# Netscale48HD_Microccontroller.net
KiCad netlist of a schematic drawn in Altium Designer
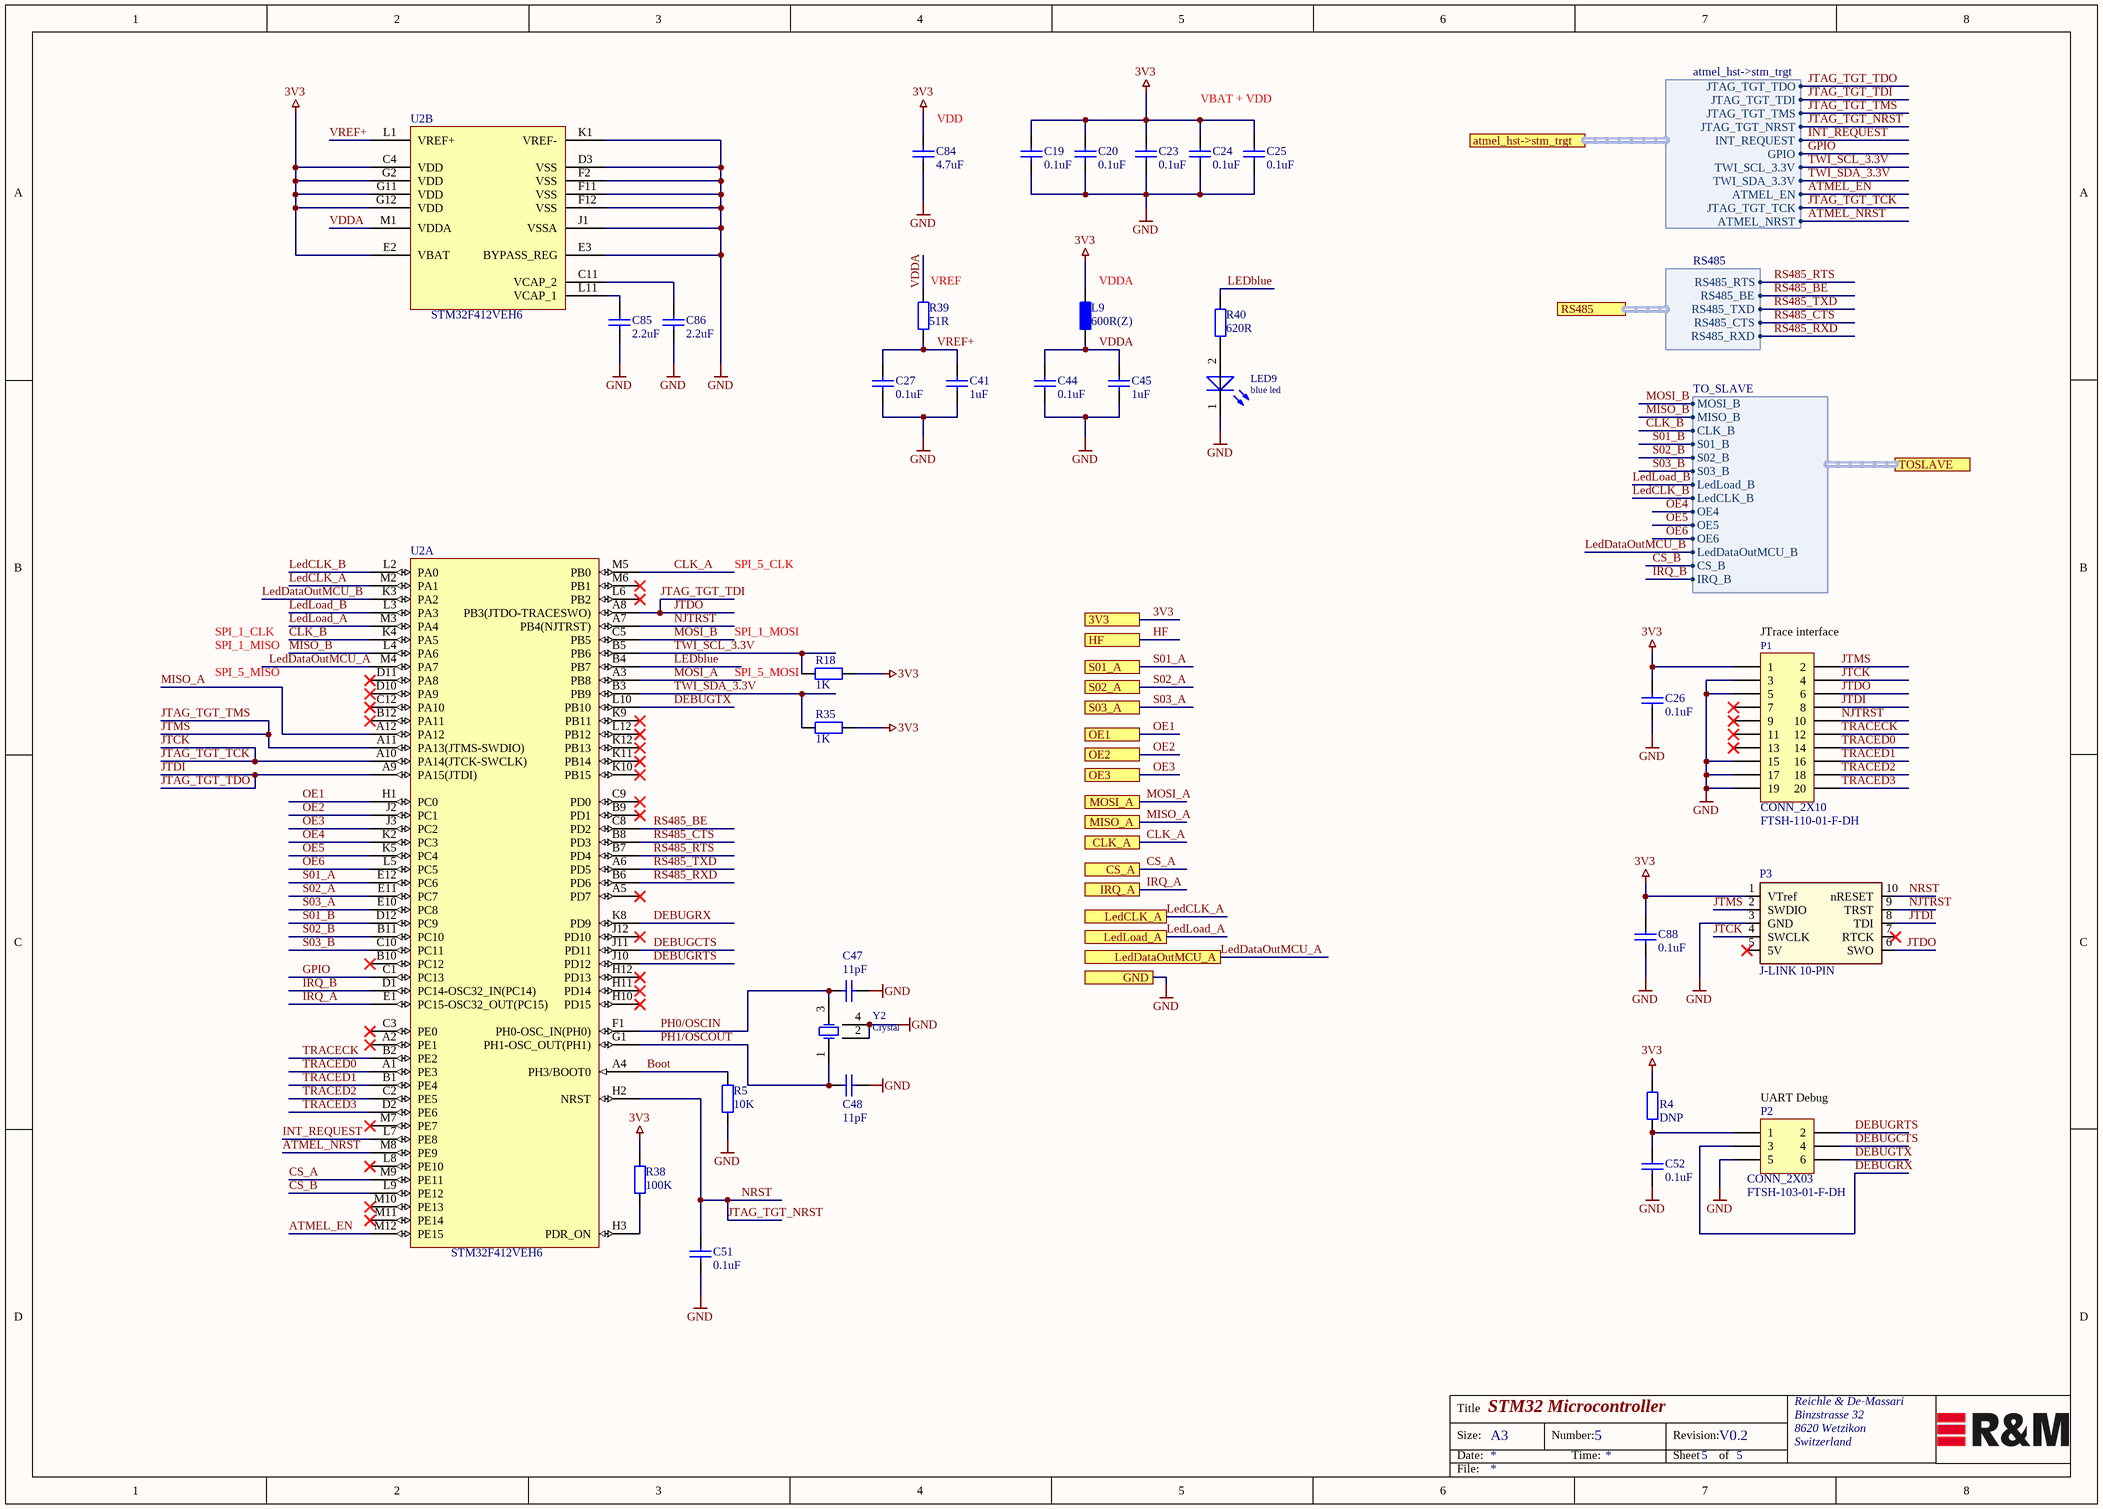
[diagram p0: Netscale48HD_Microccontroller.SchDoc]

(export (version "E")
  (design (tool "Eeschema 10.0.6"))
  (components
    (comp (ref "C19")
      (value "0.1uF")
      (footprint "Ceramic Capacitor 0402 EIA")
      (description "SMD/SMT WCAP-CSGP 0.1uF 0402 20% 10V MLCC")
      (fields (field (name "TOLERANCE") "20%") (field (name "VOLTAGE") "10VDC"))
      (libsource (lib "RDM_ALT_SCH") (part "Cap_0.1uF_0402"))
    )
    (comp (ref "C20")
      (value "0.1uF")
      (footprint "Ceramic Capacitor 0402 EIA")
      (description "SMD/SMT WCAP-CSGP 0.1uF 0402 20% 10V MLCC")
      (fields (field (name "TOLERANCE") "20%") (field (name "VOLTAGE") "10VDC"))
      (libsource (lib "RDM_ALT_SCH") (part "Cap_0.1uF_0402"))
    )
    (comp (ref "C23")
      (value "0.1uF")
      (footprint "Ceramic Capacitor 0402 EIA")
      (description "SMD/SMT WCAP-CSGP 0.1uF 0402 20% 10V MLCC")
      (fields (field (name "TOLERANCE") "20%") (field (name "VOLTAGE") "10VDC"))
      (libsource (lib "RDM_ALT_SCH") (part "Cap_0.1uF_0402"))
    )
    (comp (ref "C24")
      (value "0.1uF")
      (footprint "Ceramic Capacitor 0402 EIA")
      (description "SMD/SMT WCAP-CSGP 0.1uF 0402 20% 10V MLCC")
      (fields (field (name "TOLERANCE") "20%") (field (name "VOLTAGE") "10VDC"))
      (libsource (lib "RDM_ALT_SCH") (part "Cap_0.1uF_0402"))
    )
    (comp (ref "C25")
      (value "0.1uF")
      (footprint "Ceramic Capacitor 0402 EIA")
      (description "SMD/SMT WCAP-CSGP 0.1uF 0402 20% 10V MLCC")
      (fields (field (name "TOLERANCE") "20%") (field (name "VOLTAGE") "10VDC"))
      (libsource (lib "RDM_ALT_SCH") (part "Cap_0.1uF_0402"))
    )
    (comp (ref "C26")
      (value "0.1uF")
      (footprint "CAPC1005X55N")
      (description "SMD/SMT WCAP-CSGP 0.1uF 0402 20% 10V MLCC")
      (fields (field (name "TOLERANCE") "20%") (field (name "VOLTAGE") "10VDC"))
      (libsource (lib "RDM_Altium_Library") (part "Cap_0.1uF_0402"))
    )
    (comp (ref "C27")
      (value "0.1uF")
      (footprint "Ceramic Capacitor 0402 EIA")
      (description "SMD/SMT WCAP-CSGP 0.1uF 0402 20% 10V MLCC")
      (fields (field (name "TOLERANCE") "20%") (field (name "VOLTAGE") "10VDC"))
      (libsource (lib "RDM_ALT_SCH") (part "Cap_0.1uF_0402"))
    )
    (comp (ref "C41")
      (value "1uF")
      (footprint "Ceramic Capacitor 0402 EIA")
      (description "SMD/SMT 0402 1uF 10volts X7S 10%")
      (fields (field (name "TOLERANCE") "10%") (field (name "VOLTAGE") "10VDC"))
      (libsource (lib "RDM_ALT_SCH") (part "Cap_1uF_0402"))
    )
    (comp (ref "C44")
      (value "0.1uF")
      (footprint "Ceramic Capacitor 0402 EIA")
      (description "SMD/SMT WCAP-CSGP 0.1uF 0402 20% 10V MLCC")
      (fields (field (name "TOLERANCE") "20%") (field (name "VOLTAGE") "10VDC"))
      (libsource (lib "RDM_ALT_SCH") (part "Cap_0.1uF_0402"))
    )
    (comp (ref "C45")
      (value "1uF")
      (footprint "Ceramic Capacitor 0402 EIA")
      (description "SMD/SMT 0402 1uF 10volts X7S 10%")
      (fields (field (name "TOLERANCE") "10%") (field (name "VOLTAGE") "10VDC"))
      (libsource (lib "RDM_ALT_SCH") (part "Cap_1uF_0402"))
    )
    (comp (ref "C47")
      (value "11pF")
      (footprint "CAPC0402(1005)60_L")
      (description "SMD/SMT 0402 11pF 50volts C0G 5%")
      (fields (field (name "TOLERANCE") "5%") (field (name "VOLTAGE") "50VDC"))
      (libsource (lib "Netscale72_Panelcontroller") (part "Cap_11pF_0402"))
    )
    (comp (ref "C48")
      (value "11pF")
      (footprint "CAPC0402(1005)60_L")
      (description "SMD/SMT 0402 11pF 50volts C0G 5%")
      (fields (field (name "TOLERANCE") "5%") (field (name "VOLTAGE") "50VDC"))
      (libsource (lib "Netscale72_Panelcontroller") (part "Cap_11pF_0402"))
    )
    (comp (ref "C51")
      (value "0.1uF")
      (footprint "Ceramic Capacitor 0402 EIA")
      (description "SMD/SMT WCAP-CSGP 0.1uF 0402 20% 10V MLCC")
      (fields (field (name "TOLERANCE") "20%") (field (name "VOLTAGE") "10VDC"))
      (libsource (lib "RDM_ALT_SCH") (part "Cap_0.1uF_0402"))
    )
    (comp (ref "C52")
      (value "0.1uF")
      (footprint "Ceramic Capacitor 0402 EIA")
      (description "SMD/SMT WCAP-CSGP 0.1uF 0402 20% 10V MLCC")
      (fields (field (name "TOLERANCE") "20%") (field (name "VOLTAGE") "10VDC"))
      (libsource (lib "RDM_Altium_Library") (part "Cap_0.1uF_0402"))
    )
    (comp (ref "C84")
      (value "4.7uF")
      (footprint "Ceramic Capacitor 0603 EIA")
      (description "SMD/SMT 0603 4.7uF 10volts")
      (fields (field (name "TOLERANCE") "20%") (field (name "VOLTAGE") "10VDC"))
      (libsource (lib "RDM_ALT_SCH") (part "Cap_4.7uF_0603"))
    )
    (comp (ref "C85")
      (value "2.2uF")
      (footprint "Ceramic Capacitor 0402 EIA")
      (description "2.2µF ±20% 25V Ceramic Capacitor X5R 0402 (1005 Metric)")
      (fields (field (name "TOLERANCE") "±20%") (field (name "VOLTAGE") "25V"))
      (libsource (lib "Netscale72_Panelcontroller") (part "Cap_2.2uF_0402"))
    )
    (comp (ref "C86")
      (value "2.2uF")
      (footprint "Ceramic Capacitor 0402 EIA")
      (description "2.2µF ±20% 25V Ceramic Capacitor X5R 0402 (1005 Metric)")
      (fields (field (name "TOLERANCE") "±20%") (field (name "VOLTAGE") "25V"))
      (libsource (lib "Netscale72_Panelcontroller") (part "Cap_2.2uF_0402"))
    )
    (comp (ref "C88")
      (value "0.1uF")
      (footprint "Ceramic Capacitor 0402 EIA")
      (description "SMD/SMT WCAP-CSGP 0.1uF 0402 20% 10V MLCC")
      (fields (field (name "TOLERANCE") "20%") (field (name "VOLTAGE") "10VDC"))
      (libsource (lib "RDM_ALT_SCH") (part "Cap_0.1uF_0402"))
    )
    (comp (ref "L9")
      (value "600R(Z)")
      (footprint "Inductor 0603 EIA")
      (description "Ferritperlen MULTILYR CHP BD 0603 600OHMS 25%")
      (fields (field (name "TOLERANCE") "25%") (field (name "MANUFACTURER") "Taiyo Yuden"))
      (libsource (lib "RDM_ALT_SCH") (part "Ind_600R_0603"))
    )
    (comp (ref "LED9")
      (value "blue led")
      (footprint "Kingbright_SMD_2_RWH")
      (description "blue, 1.6 x 0.6 mm Right Angle SMD Chip LED Lamp")
      (fields (field (name "MANUFACTURER") "Kingbright"))
      (libsource (lib "RDM_Altium_Library") (part "APA1606VBC/D"))
    )
    (comp (ref "P1")
      (value "CONN_2X10")
      (footprint "FTSH-110-01-F-DH")
      (description "20Pin, 2Rows, side/horizontally, MICRO LOW-PROFILE TERMINAL STRIPS")
      (fields (field (name "MANUFACTURER") "Samtec") (field (name "MANUFACTURER PARTNR") "FTSH-110-01-F-DH"))
      (libsource (lib "RDM_Altium_Library") (part "CONN_2X10_FTSH-110-01-F-DH"))
    )
    (comp (ref "P2")
      (value "CONN_2X03")
      (footprint "FTSH-103-01-F-DH")
      (description "6Pin, 2Rows, MICRO LOW-PROFILE TERMINAL STRIPS")
      (fields (field (name "MANUFACTURER") "Samtec") (field (name "MANUFACTURER PARTNR") "FTSH-103-01-F-DH"))
      (libsource (lib "RDM_Altium_Library") (part "CONN_2X03_FTSH-103-01-F-DH"))
    )
    (comp (ref "P3")
      (value "J-LINK 10-PIN")
      (footprint "CONN-SEGGER-10-PIN")
      (description "Segger, J-Link 10-pin Needle Adapter")
      (libsource (lib "RDM_ALT_SCH") (part "CONN_Segger_10_PIN"))
    )
    (comp (ref "R4")
      (value "DNP")
      (footprint "RESC1005X40N")
      (description "Resistor: do not populate")
      (fields (field (name "MANUFACTURER") "do not populate"))
      (libsource (lib "RDM_Altium_Library") (part "Res_DNP_0402"))
    )
    (comp (ref "R5")
      (value "10K")
      (footprint "RES-0402[1005] - RFL")
      (description "10K 0.063W 1% 0402 (1005 Metric)  SMD")
      (fields (field (name "TOLERANCE") "±1%") (field (name "MANUFACTURER") "Yageo"))
      (libsource (lib "RDM_ALT_SCH") (part "PassResBas0402-00623-A.3"))
    )
    (comp (ref "R18")
      (value "1K")
      (footprint "Resistor 0402 EIA")
      (description "Thick Film Resistors - SMD CRGCQ 0402 1K0 1% SMD Resistor")
      (fields (field (name "TOLERANCE") "±1%") (field (name "POWER") "1/16W"))
      (libsource (lib "RDM_ALT_SCH") (part "Res_1K_0402"))
    )
    (comp (ref "R35")
      (value "1K")
      (footprint "Resistor 0402 EIA")
      (description "Thick Film Resistors - SMD CRGCQ 0402 1K0 1% SMD Resistor")
      (fields (field (name "TOLERANCE") "±1%") (field (name "POWER") "1/16W"))
      (libsource (lib "RDM_ALT_SCH") (part "Res_1K_0402"))
    )
    (comp (ref "R38")
      (value "100K")
      (footprint "Resistor 0402 EIA")
      (description "100 kOhm Resistor 0402")
      (fields (field (name "POWER") "63mW") (field (name "MANUFACTURER") "Vishay"))
      (libsource (lib "Netscale72_Panelcontroller") (part "Res_100K_0402"))
    )
    (comp (ref "R39")
      (value "51R")
      (footprint "Resistor 0402 EIA")
      (description "Resistor")
      (fields (field (name "TOLERANCE") "5%") (field (name "POWER") "62.5mW"))
      (libsource (lib "RDM_ALT_SCH") (part "Res_51R_0402"))
    )
    (comp (ref "R40")
      (value "620R")
      (footprint "Resistor 0402 EIA")
      (description "SMD 1/16W 620ohm 0.5%")
      (fields (field (name "TOLERANCE") "0.5%") (field (name "POWER") "62.5mW"))
      (libsource (lib "RDM_ALT_SCH") (part "Res_620R_0402"))
    )
    (comp (ref "U2")
      (value "STM32F412VEH6")
      (footprint "STM_UFBGA100 7x7x0.6_100_R")
      (fields (field (name "MANUFACTURER") "STMicroelectronics"))
      (libsource (lib "RDM_ALT_SCH") (part "STM_STM32F412VEH6_UFBGA100 7x7x0.6_100"))
    )
    (comp (ref "Y2")
      (value "Crystal")
      (footprint "ECS_ECX-2236_4_R")
      (description "Quarz 24MHz-10pF 10ppm-10C +70C")
      (fields
        (field (name "MANUFACTURER PART NUMBER") "ECS-240-10-36-CKL-TR")
        (field (name "MANUFACTURER") "ECS")
      )
      (libsource (lib "RDM_ALT_SCH") (part "ECS-240-10-36-CKL-TR"))
    )
  )
  (nets
    (net (code "4") (name "/ATMEL_EN") (class "Default")
      (node (ref "U2") (pin "M12") (pinfunction "PE15_M12") (pintype "bidirectional"))
    )
    (net (code "5") (name "/ATMEL_NRST") (class "Default")
      (node (ref "U2") (pin "M8") (pinfunction "PE9_M8") (pintype "bidirectional"))
    )
    (net (code "6") (name "/Boot") (class "Default")
      (node (ref "R5") (pin "1") (pinfunction "1_1") (pintype "passive"))
      (node (ref "U2") (pin "A4") (pinfunction "PH3/BOOT0_A4") (pintype "input"))
    )
    (net (code "7") (name "/CLK_A") (class "Default")
      (node (ref "U2") (pin "M5") (pinfunction "PB0_M5") (pintype "bidirectional"))
    )
    (net (code "8") (name "/CLK_B") (class "Default")
      (node (ref "U2") (pin "K4") (pinfunction "PA5_K4") (pintype "bidirectional"))
    )
    (net (code "9") (name "/CS_A") (class "Default")
      (node (ref "U2") (pin "M9") (pinfunction "PE11_M9") (pintype "bidirectional"))
    )
    (net (code "10") (name "/CS_B") (class "Default")
      (node (ref "U2") (pin "L9") (pinfunction "PE12_L9") (pintype "bidirectional"))
    )
    (net (code "11") (name "/DEBUGCTS") (class "Default")
      (node (ref "P2") (pin "4") (pinfunction "4_4") (pintype "passive"))
      (node (ref "U2") (pin "J11") (pinfunction "PD11_J11") (pintype "bidirectional"))
    )
    (net (code "12") (name "/DEBUGRTS") (class "Default")
      (node (ref "P2") (pin "2") (pinfunction "2_2") (pintype "passive"))
      (node (ref "U2") (pin "J10") (pinfunction "PD12_J10") (pintype "bidirectional"))
    )
    (net (code "13") (name "/DEBUGRX") (class "Default")
      (node (ref "P2") (pin "3") (pinfunction "3_3") (pintype "passive"))
      (node (ref "U2") (pin "K8") (pinfunction "PD9_K8") (pintype "bidirectional"))
    )
    (net (code "14") (name "/DEBUGTX") (class "Default")
      (node (ref "P2") (pin "6") (pinfunction "6_6") (pintype "passive"))
      (node (ref "U2") (pin "L10") (pinfunction "PB10_L10") (pintype "bidirectional"))
    )
    (net (code "15") (name "/GPIO") (class "Default")
      (node (ref "U2") (pin "C1") (pinfunction "PC13_C1") (pintype "bidirectional"))
    )
    (net (code "17") (name "/INT_REQUEST") (class "Default")
      (node (ref "U2") (pin "L7") (pinfunction "PE8_L7") (pintype "bidirectional"))
    )
    (net (code "18") (name "/IRQ_A") (class "Default")
      (node (ref "U2") (pin "E1") (pinfunction "PC15-OSC32_OUT(PC15)_E1") (pintype "bidirectional"))
    )
    (net (code "19") (name "/IRQ_B") (class "Default")
      (node (ref "U2") (pin "D1") (pinfunction "PC14-OSC32_IN(PC14)_D1") (pintype "bidirectional"))
    )
    (net (code "20") (name "/JTAG_TGT_NRST") (class "Default")
      (node (ref "C51") (pin "2") (pinfunction "2_2") (pintype "passive"))
      (node (ref "P3") (pin "10") (pinfunction "nRESET_10") (pintype "passive"))
      (node (ref "U2") (pin "H2") (pinfunction "NRST_H2") (pintype "bidirectional"))
    )
    (net (code "21") (name "/JTAG_TGT_TCK") (class "Default")
      (node (ref "P1") (pin "4") (pinfunction "4_4") (pintype "passive"))
      (node (ref "P3") (pin "4") (pinfunction "SWCLK_4") (pintype "passive"))
      (node (ref "U2") (pin "A10") (pinfunction "PA14(JTCK-SWCLK)_A10") (pintype "bidirectional"))
    )
    (net (code "22") (name "/JTAG_TGT_TDI") (class "Default")
      (node (ref "P1") (pin "6") (pinfunction "6_6") (pintype "passive"))
      (node (ref "P3") (pin "6") (pinfunction "SWO_6") (pintype "passive"))
      (node (ref "U2") (pin "A8") (pinfunction "PB3(JTDO-TRACESWO)_A8") (pintype "bidirectional"))
    )
    (net (code "23") (name "/JTAG_TGT_TDO") (class "Default")
      (node (ref "P1") (pin "8") (pinfunction "8_8") (pintype "passive"))
      (node (ref "P3") (pin "8") (pinfunction "TDI_8") (pintype "passive"))
      (node (ref "U2") (pin "A9") (pinfunction "PA15(JTDI)_A9") (pintype "bidirectional"))
    )
    (net (code "24") (name "/JTAG_TGT_TMS") (class "Default")
      (node (ref "P1") (pin "2") (pinfunction "2_2") (pintype "passive"))
      (node (ref "P3") (pin "2") (pinfunction "SWDIO_2") (pintype "passive"))
      (node (ref "U2") (pin "A11") (pinfunction "PA13(JTMS-SWDIO)_A11") (pintype "bidirectional"))
    )
    (net (code "25") (name "/LEDblue") (class "Default")
      (node (ref "R40") (pin "1") (pinfunction "1_1") (pintype "passive"))
      (node (ref "U2") (pin "B4") (pinfunction "PB7_B4") (pintype "bidirectional"))
    )
    (net (code "26") (name "/LedCLK_A") (class "Default")
      (node (ref "U2") (pin "M2") (pinfunction "PA1_M2") (pintype "bidirectional"))
    )
    (net (code "27") (name "/LedCLK_B") (class "Default")
      (node (ref "U2") (pin "L2") (pinfunction "PA0_L2") (pintype "bidirectional"))
    )
    (net (code "28") (name "/LedDataOutMCU_A") (class "Default")
      (node (ref "U2") (pin "M4") (pinfunction "PA7_M4") (pintype "bidirectional"))
    )
    (net (code "29") (name "/LedDataOutMCU_B") (class "Default")
      (node (ref "U2") (pin "K3") (pinfunction "PA2_K3") (pintype "bidirectional"))
    )
    (net (code "30") (name "/LedLoad_A") (class "Default")
      (node (ref "U2") (pin "M3") (pinfunction "PA4_M3") (pintype "bidirectional"))
    )
    (net (code "31") (name "/LedLoad_B") (class "Default")
      (node (ref "U2") (pin "L3") (pinfunction "PA3_L3") (pintype "bidirectional"))
    )
    (net (code "32") (name "/MISO_A") (class "Default")
      (node (ref "U2") (pin "A12") (pinfunction "PA12_A12") (pintype "bidirectional"))
    )
    (net (code "33") (name "/MISO_B") (class "Default")
      (node (ref "U2") (pin "L4") (pinfunction "PA6_L4") (pintype "bidirectional"))
    )
    (net (code "34") (name "/MOSI_A") (class "Default")
      (node (ref "U2") (pin "A3") (pinfunction "PB8_A3") (pintype "bidirectional"))
    )
    (net (code "35") (name "/MOSI_B") (class "Default")
      (node (ref "U2") (pin "C5") (pinfunction "PB5_C5") (pintype "bidirectional"))
    )
    (net (code "36") (name "/NJTRST") (class "Default")
      (node (ref "P1") (pin "10") (pinfunction "10_10") (pintype "passive"))
      (node (ref "P3") (pin "9") (pinfunction "TRST_9") (pintype "passive"))
      (node (ref "U2") (pin "A7") (pinfunction "PB4(NJTRST)_A7") (pintype "bidirectional"))
    )
    (net (code "37") (name "/OE1") (class "Default")
      (node (ref "U2") (pin "H1") (pinfunction "PC0_H1") (pintype "bidirectional"))
    )
    (net (code "38") (name "/OE2") (class "Default")
      (node (ref "U2") (pin "J2") (pinfunction "PC1_J2") (pintype "bidirectional"))
    )
    (net (code "39") (name "/OE3") (class "Default")
      (node (ref "U2") (pin "J3") (pinfunction "PC2_J3") (pintype "bidirectional"))
    )
    (net (code "40") (name "/OE4") (class "Default")
      (node (ref "U2") (pin "K2") (pinfunction "PC3_K2") (pintype "bidirectional"))
    )
    (net (code "41") (name "/OE5") (class "Default")
      (node (ref "U2") (pin "K5") (pinfunction "PC4_K5") (pintype "bidirectional"))
    )
    (net (code "42") (name "/OE6") (class "Default")
      (node (ref "U2") (pin "L5") (pinfunction "PC5_L5") (pintype "bidirectional"))
    )
    (net (code "43") (name "/PH0{slash}OSCIN") (class "Default")
      (node (ref "C47") (pin "1") (pinfunction "1_1") (pintype "passive"))
      (node (ref "U2") (pin "F1") (pinfunction "PH0-OSC_IN(PH0)_F1") (pintype "bidirectional"))
      (node (ref "Y2") (pin "3") (pinfunction "OSC2_3") (pintype "passive"))
    )
    (net (code "44") (name "/PH1{slash}OSCOUT") (class "Default")
      (node (ref "C48") (pin "1") (pinfunction "1_1") (pintype "passive"))
      (node (ref "U2") (pin "G1") (pinfunction "PH1-OSC_OUT(PH1)_G1") (pintype "bidirectional"))
      (node (ref "Y2") (pin "1") (pinfunction "OSC1_1") (pintype "passive"))
    )
    (net (code "45") (name "/RS485_BE") (class "Default")
      (node (ref "U2") (pin "C8") (pinfunction "PD2_C8") (pintype "bidirectional"))
    )
    (net (code "46") (name "/RS485_CTS") (class "Default")
      (node (ref "U2") (pin "B8") (pinfunction "PD3_B8") (pintype "bidirectional"))
    )
    (net (code "47") (name "/RS485_RTS") (class "Default")
      (node (ref "U2") (pin "B7") (pinfunction "PD4_B7") (pintype "bidirectional"))
    )
    (net (code "48") (name "/RS485_RXD") (class "Default")
      (node (ref "U2") (pin "B6") (pinfunction "PD6_B6") (pintype "bidirectional"))
    )
    (net (code "49") (name "/RS485_TXD") (class "Default")
      (node (ref "U2") (pin "A6") (pinfunction "PD5_A6") (pintype "bidirectional"))
    )
    (net (code "50") (name "/S01_A") (class "Default")
      (node (ref "U2") (pin "E12") (pinfunction "PC6_E12") (pintype "bidirectional"))
    )
    (net (code "51") (name "/S01_B") (class "Default")
      (node (ref "U2") (pin "D12") (pinfunction "PC9_D12") (pintype "bidirectional"))
    )
    (net (code "52") (name "/S02_A") (class "Default")
      (node (ref "U2") (pin "E11") (pinfunction "PC7_E11") (pintype "bidirectional"))
    )
    (net (code "53") (name "/S02_B") (class "Default")
      (node (ref "U2") (pin "B11") (pinfunction "PC10_B11") (pintype "bidirectional"))
    )
    (net (code "54") (name "/S03_A") (class "Default")
      (node (ref "U2") (pin "E10") (pinfunction "PC8_E10") (pintype "bidirectional"))
    )
    (net (code "55") (name "/S03_B") (class "Default")
      (node (ref "U2") (pin "C10") (pinfunction "PC11_C10") (pintype "bidirectional"))
    )
    (net (code "56") (name "/TRACECK") (class "Default")
      (node (ref "P1") (pin "12") (pinfunction "12_12") (pintype "passive"))
      (node (ref "U2") (pin "B2") (pinfunction "PE2_B2") (pintype "bidirectional"))
    )
    (net (code "57") (name "/TRACED0") (class "Default")
      (node (ref "P1") (pin "14") (pinfunction "14_14") (pintype "passive"))
      (node (ref "U2") (pin "A1") (pinfunction "PE3_A1") (pintype "bidirectional"))
    )
    (net (code "58") (name "/TRACED1") (class "Default")
      (node (ref "P1") (pin "16") (pinfunction "16_16") (pintype "passive"))
      (node (ref "U2") (pin "B1") (pinfunction "PE4_B1") (pintype "bidirectional"))
    )
    (net (code "59") (name "/TRACED2") (class "Default")
      (node (ref "P1") (pin "18") (pinfunction "18_18") (pintype "passive"))
      (node (ref "U2") (pin "C2") (pinfunction "PE5_C2") (pintype "bidirectional"))
    )
    (net (code "60") (name "/TRACED3") (class "Default")
      (node (ref "P1") (pin "20") (pinfunction "20_20") (pintype "passive"))
      (node (ref "U2") (pin "D2") (pinfunction "PE6_D2") (pintype "bidirectional"))
    )
    (net (code "61") (name "/TWI_SCL_3.3V") (class "Default")
      (node (ref "R18") (pin "1") (pinfunction "1_1") (pintype "passive"))
      (node (ref "U2") (pin "B5") (pinfunction "PB6_B5") (pintype "bidirectional"))
    )
    (net (code "62") (name "/TWI_SDA_3.3V") (class "Default")
      (node (ref "R35") (pin "1") (pinfunction "1_1") (pintype "passive"))
      (node (ref "U2") (pin "B3") (pinfunction "PB9_B3") (pintype "bidirectional"))
    )
    (net (code "63") (name "/VDDA") (class "Default")
      (node (ref "C44") (pin "2") (pinfunction "2_2") (pintype "passive"))
      (node (ref "C45") (pin "2") (pinfunction "2_2") (pintype "passive"))
      (node (ref "L9") (pin "2") (pinfunction "2_2") (pintype "passive"))
      (node (ref "R39") (pin "1") (pinfunction "1_1") (pintype "passive"))
      (node (ref "U2") (pin "M1") (pinfunction "VDDA_M1") (pintype "power_in"))
    )
    (net (code "64") (name "/VREF+") (class "Default")
      (node (ref "C27") (pin "2") (pinfunction "2_2") (pintype "passive"))
      (node (ref "C41") (pin "2") (pinfunction "2_2") (pintype "passive"))
      (node (ref "R39") (pin "2") (pinfunction "2_2") (pintype "passive"))
      (node (ref "U2") (pin "L1") (pinfunction "VREF+_L1") (pintype "power_in"))
    )
    (net (code "68") (name "3V3") (class "Default")
      (node (ref "C19") (pin "2") (pinfunction "2_2") (pintype "passive"))
      (node (ref "C20") (pin "2") (pinfunction "2_2") (pintype "passive"))
      (node (ref "C23") (pin "2") (pinfunction "2_2") (pintype "passive"))
      (node (ref "C24") (pin "2") (pinfunction "2_2") (pintype "passive"))
      (node (ref "C25") (pin "2") (pinfunction "2_2") (pintype "passive"))
      (node (ref "C26") (pin "2") (pinfunction "2_2") (pintype "passive"))
      (node (ref "C84") (pin "2") (pinfunction "2_2") (pintype "passive"))
      (node (ref "C88") (pin "2") (pinfunction "2_2") (pintype "passive"))
      (node (ref "L9") (pin "1") (pinfunction "1_1") (pintype "passive"))
      (node (ref "P1") (pin "1") (pinfunction "1_1") (pintype "passive"))
      (node (ref "P3") (pin "1") (pinfunction "VTref_1") (pintype "passive"))
      (node (ref "R18") (pin "2") (pinfunction "2_2") (pintype "passive"))
      (node (ref "R35") (pin "2") (pinfunction "2_2") (pintype "passive"))
      (node (ref "R38") (pin "1") (pinfunction "1_1") (pintype "passive"))
      (node (ref "R4") (pin "2") (pinfunction "2_2") (pintype "passive"))
      (node (ref "U2") (pin "C4") (pinfunction "VDD_C4") (pintype "power_in"))
      (node (ref "U2") (pin "E2") (pinfunction "VBAT_E2") (pintype "power_in"))
      (node (ref "U2") (pin "G11") (pinfunction "VDD_G11") (pintype "power_in"))
      (node (ref "U2") (pin "G12") (pinfunction "VDD_G12") (pintype "power_in"))
      (node (ref "U2") (pin "G2") (pinfunction "VDD_G2") (pintype "power_in"))
    )
    (net (code "69") (name "GND") (class "Default")
      (node (ref "C19") (pin "1") (pinfunction "1_1") (pintype "passive"))
      (node (ref "C20") (pin "1") (pinfunction "1_1") (pintype "passive"))
      (node (ref "C23") (pin "1") (pinfunction "1_1") (pintype "passive"))
      (node (ref "C24") (pin "1") (pinfunction "1_1") (pintype "passive"))
      (node (ref "C25") (pin "1") (pinfunction "1_1") (pintype "passive"))
      (node (ref "C26") (pin "1") (pinfunction "1_1") (pintype "passive"))
      (node (ref "C27") (pin "1") (pinfunction "1_1") (pintype "passive"))
      (node (ref "C41") (pin "1") (pinfunction "1_1") (pintype "passive"))
      (node (ref "C44") (pin "1") (pinfunction "1_1") (pintype "passive"))
      (node (ref "C45") (pin "1") (pinfunction "1_1") (pintype "passive"))
      (node (ref "C47") (pin "2") (pinfunction "2_2") (pintype "passive"))
      (node (ref "C48") (pin "2") (pinfunction "2_2") (pintype "passive"))
      (node (ref "C51") (pin "1") (pinfunction "1_1") (pintype "passive"))
      (node (ref "C52") (pin "1") (pinfunction "1_1") (pintype "passive"))
      (node (ref "C84") (pin "1") (pinfunction "1_1") (pintype "passive"))
      (node (ref "C85") (pin "1") (pinfunction "1_1") (pintype "passive"))
      (node (ref "C86") (pin "1") (pinfunction "1_1") (pintype "passive"))
      (node (ref "C88") (pin "1") (pinfunction "1_1") (pintype "passive"))
      (node (ref "LED9") (pin "1") (pinfunction "K_1") (pintype "passive"))
      (node (ref "P1") (pin "15") (pinfunction "15_15") (pintype "passive"))
      (node (ref "P1") (pin "17") (pinfunction "17_17") (pintype "passive"))
      (node (ref "P1") (pin "19") (pinfunction "19_19") (pintype "passive"))
      (node (ref "P1") (pin "3") (pinfunction "3_3") (pintype "passive"))
      (node (ref "P1") (pin "5") (pinfunction "5_5") (pintype "passive"))
      (node (ref "P2") (pin "5") (pinfunction "5_5") (pintype "passive"))
      (node (ref "P3") (pin "3") (pinfunction "GND_3") (pintype "passive"))
      (node (ref "R5") (pin "2") (pinfunction "2_2") (pintype "passive"))
      (node (ref "U2") (pin "D3") (pinfunction "VSS_D3") (pintype "power_in"))
      (node (ref "U2") (pin "E3") (pinfunction "BYPASS_REG_E3") (pintype "power_in"))
      (node (ref "U2") (pin "F11") (pinfunction "VSS_F11") (pintype "power_in"))
      (node (ref "U2") (pin "F12") (pinfunction "VSS_F12") (pintype "power_in"))
      (node (ref "U2") (pin "F2") (pinfunction "VSS_F2") (pintype "power_in"))
      (node (ref "U2") (pin "J1") (pinfunction "VSSA_J1") (pintype "power_in"))
      (node (ref "U2") (pin "K1") (pinfunction "VREF-_K1") (pintype "power_in"))
      (node (ref "Y2") (pin "2") (pinfunction "OSC2_2") (pintype "passive"))
      (node (ref "Y2") (pin "4") (pinfunction "OSC3_4") (pintype "passive"))
    )
    (net (code "70") (name "Net-(C52-Pad2)") (class "Default")
      (node (ref "C52") (pin "2") (pinfunction "2_2") (pintype "passive"))
      (node (ref "P2") (pin "1") (pinfunction "1_1") (pintype "passive"))
      (node (ref "R4") (pin "1") (pinfunction "1_1") (pintype "passive"))
    )
    (net (code "71") (name "Net-(LED9-A)") (class "Default")
      (node (ref "LED9") (pin "2") (pinfunction "A_2") (pintype "passive"))
      (node (ref "R40") (pin "2") (pinfunction "2_2") (pintype "passive"))
    )
    (net (code "72") (name "Net-(U2A-PDR_ON)") (class "Default")
      (node (ref "R38") (pin "2") (pinfunction "2_2") (pintype "passive"))
      (node (ref "U2") (pin "H3") (pinfunction "PDR_ON_H3") (pintype "bidirectional"))
    )
    (net (code "73") (name "Net-(U2B-VCAP_1)") (class "Default")
      (node (ref "C85") (pin "2") (pinfunction "2_2") (pintype "passive"))
      (node (ref "U2") (pin "L11") (pinfunction "VCAP_1_L11") (pintype "power_in"))
    )
    (net (code "74") (name "Net-(U2B-VCAP_2)") (class "Default")
      (node (ref "C86") (pin "2") (pinfunction "2_2") (pintype "passive"))
      (node (ref "U2") (pin "C11") (pinfunction "VCAP_2_C11") (pintype "power_in"))
    )
    (net (code "75") (name "unconnected-(P1-Pad7)") (class "Default")
      (node (ref "P1") (pin "7") (pinfunction "7_7") (pintype "passive+no_connect"))
    )
    (net (code "76") (name "unconnected-(P1-Pad9)") (class "Default")
      (node (ref "P1") (pin "9") (pinfunction "9_9") (pintype "passive+no_connect"))
    )
    (net (code "77") (name "unconnected-(P1-Pad11)") (class "Default")
      (node (ref "P1") (pin "11") (pinfunction "11_11") (pintype "passive+no_connect"))
    )
    (net (code "78") (name "unconnected-(P1-Pad13)") (class "Default")
      (node (ref "P1") (pin "13") (pinfunction "13_13") (pintype "passive+no_connect"))
    )
    (net (code "79") (name "unconnected-(P3-5V-Pad5)") (class "Default")
      (node (ref "P3") (pin "5") (pinfunction "5V_5") (pintype "passive+no_connect"))
    )
    (net (code "80") (name "unconnected-(P3-RTCK-Pad7)") (class "Default")
      (node (ref "P3") (pin "7") (pinfunction "RTCK_7") (pintype "passive+no_connect"))
    )
    (net (code "81") (name "unconnected-(U2A-PA8-PadD11)") (class "Default")
      (node (ref "U2") (pin "D11") (pinfunction "PA8_D11") (pintype "bidirectional+no_connect"))
    )
    (net (code "82") (name "unconnected-(U2A-PA9-PadD10)") (class "Default")
      (node (ref "U2") (pin "D10") (pinfunction "PA9_D10") (pintype "bidirectional+no_connect"))
    )
    (net (code "83") (name "unconnected-(U2A-PA10-PadC12)") (class "Default")
      (node (ref "U2") (pin "C12") (pinfunction "PA10_C12") (pintype "bidirectional+no_connect"))
    )
    (net (code "84") (name "unconnected-(U2A-PA11-PadB12)") (class "Default")
      (node (ref "U2") (pin "B12") (pinfunction "PA11_B12") (pintype "bidirectional+no_connect"))
    )
    (net (code "85") (name "unconnected-(U2A-PB1-PadM6)") (class "Default")
      (node (ref "U2") (pin "M6") (pinfunction "PB1_M6") (pintype "bidirectional+no_connect"))
    )
    (net (code "86") (name "unconnected-(U2A-PB2-PadL6)") (class "Default")
      (node (ref "U2") (pin "L6") (pinfunction "PB2_L6") (pintype "bidirectional+no_connect"))
    )
    (net (code "87") (name "unconnected-(U2A-PB11-PadK9)") (class "Default")
      (node (ref "U2") (pin "K9") (pinfunction "PB11_K9") (pintype "bidirectional+no_connect"))
    )
    (net (code "88") (name "unconnected-(U2A-PB12-PadL12)") (class "Default")
      (node (ref "U2") (pin "L12") (pinfunction "PB12_L12") (pintype "bidirectional+no_connect"))
    )
    (net (code "89") (name "unconnected-(U2A-PB13-PadK12)") (class "Default")
      (node (ref "U2") (pin "K12") (pinfunction "PB13_K12") (pintype "bidirectional+no_connect"))
    )
    (net (code "90") (name "unconnected-(U2A-PB14-PadK11)") (class "Default")
      (node (ref "U2") (pin "K11") (pinfunction "PB14_K11") (pintype "bidirectional+no_connect"))
    )
    (net (code "91") (name "unconnected-(U2A-PB15-PadK10)") (class "Default")
      (node (ref "U2") (pin "K10") (pinfunction "PB15_K10") (pintype "bidirectional+no_connect"))
    )
    (net (code "92") (name "unconnected-(U2A-PC12-PadB10)") (class "Default")
      (node (ref "U2") (pin "B10") (pinfunction "PC12_B10") (pintype "bidirectional+no_connect"))
    )
    (net (code "93") (name "unconnected-(U2A-PD0-PadC9)") (class "Default")
      (node (ref "U2") (pin "C9") (pinfunction "PD0_C9") (pintype "bidirectional+no_connect"))
    )
    (net (code "94") (name "unconnected-(U2A-PD1-PadB9)") (class "Default")
      (node (ref "U2") (pin "B9") (pinfunction "PD1_B9") (pintype "bidirectional+no_connect"))
    )
    (net (code "95") (name "unconnected-(U2A-PD7-PadA5)") (class "Default")
      (node (ref "U2") (pin "A5") (pinfunction "PD7_A5") (pintype "bidirectional+no_connect"))
    )
    (net (code "96") (name "unconnected-(U2A-PD10-PadJ12)") (class "Default")
      (node (ref "U2") (pin "J12") (pinfunction "PD10_J12") (pintype "bidirectional+no_connect"))
    )
    (net (code "97") (name "unconnected-(U2A-PD13-PadH12)") (class "Default")
      (node (ref "U2") (pin "H12") (pinfunction "PD13_H12") (pintype "bidirectional+no_connect"))
    )
    (net (code "98") (name "unconnected-(U2A-PD14-PadH11)") (class "Default")
      (node (ref "U2") (pin "H11") (pinfunction "PD14_H11") (pintype "bidirectional+no_connect"))
    )
    (net (code "99") (name "unconnected-(U2A-PD15-PadH10)") (class "Default")
      (node (ref "U2") (pin "H10") (pinfunction "PD15_H10") (pintype "bidirectional+no_connect"))
    )
    (net (code "100") (name "unconnected-(U2A-PE0-PadC3)") (class "Default")
      (node (ref "U2") (pin "C3") (pinfunction "PE0_C3") (pintype "bidirectional+no_connect"))
    )
    (net (code "101") (name "unconnected-(U2A-PE1-PadA2)") (class "Default")
      (node (ref "U2") (pin "A2") (pinfunction "PE1_A2") (pintype "bidirectional+no_connect"))
    )
    (net (code "102") (name "unconnected-(U2A-PE7-PadM7)") (class "Default")
      (node (ref "U2") (pin "M7") (pinfunction "PE7_M7") (pintype "bidirectional+no_connect"))
    )
    (net (code "103") (name "unconnected-(U2A-PE10-PadL8)") (class "Default")
      (node (ref "U2") (pin "L8") (pinfunction "PE10_L8") (pintype "bidirectional+no_connect"))
    )
    (net (code "104") (name "unconnected-(U2A-PE13-PadM10)") (class "Default")
      (node (ref "U2") (pin "M10") (pinfunction "PE13_M10") (pintype "bidirectional+no_connect"))
    )
    (net (code "105") (name "unconnected-(U2A-PE14-PadM11)") (class "Default")
      (node (ref "U2") (pin "M11") (pinfunction "PE14_M11") (pintype "bidirectional+no_connect"))
    )
  )
)
